# AJH_ss12144_01_4hp.net
KiCad netlist of a schematic drawn in EAGLE
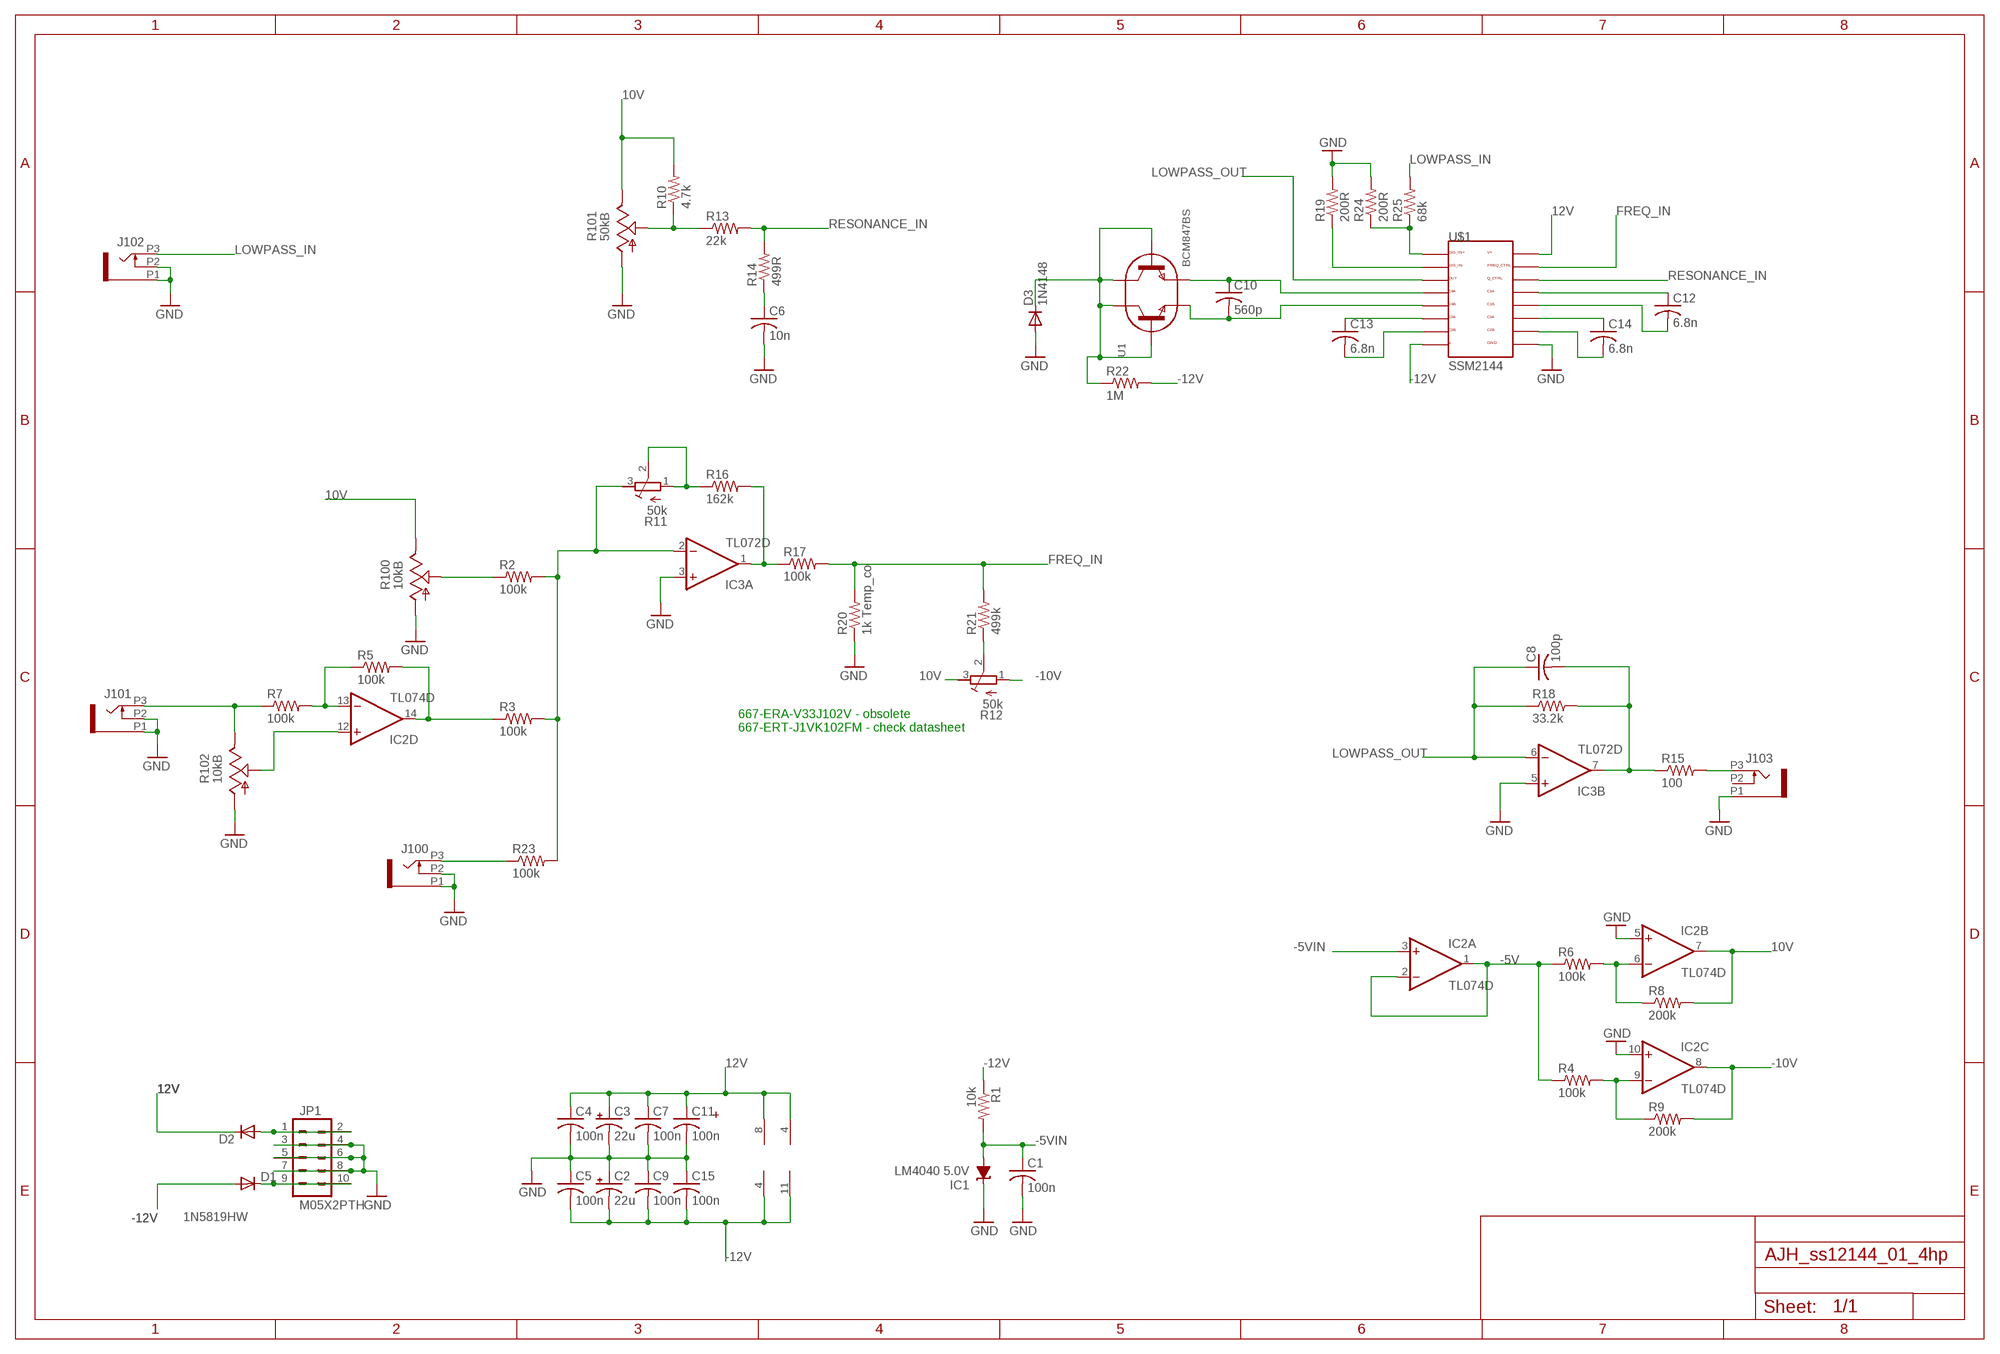
[diagram p0: schematic, sheet 1]

(export (version "E")
  (design (tool "Eeschema 10.0.6"))
  (components
    (comp (ref "C1")
      (value "100n")
      (footprint "eagle-import:C0603")
      (libsource (lib "eagle-import") (part "C-USC0603"))
    )
    (comp (ref "C2")
      (value "22u")
      (footprint "eagle-import:PANASONIC_B")
      (libsource (lib "eagle-import") (part "CPOL-USB"))
    )
    (comp (ref "C3")
      (value "22u")
      (footprint "eagle-import:PANASONIC_B")
      (libsource (lib "eagle-import") (part "CPOL-USB"))
    )
    (comp (ref "C4")
      (value "100n")
      (footprint "eagle-import:C0603")
      (libsource (lib "eagle-import") (part "C-USC0603"))
    )
    (comp (ref "C5")
      (value "100n")
      (footprint "eagle-import:C0603")
      (libsource (lib "eagle-import") (part "C-USC0603"))
    )
    (comp (ref "C6")
      (value "10n")
      (footprint "eagle-import:C0603")
      (libsource (lib "eagle-import") (part "C-USC0603"))
    )
    (comp (ref "C7")
      (value "100n")
      (footprint "eagle-import:C0603")
      (libsource (lib "eagle-import") (part "C-USC0603"))
    )
    (comp (ref "C8")
      (value "100p")
      (footprint "eagle-import:C0603")
      (libsource (lib "eagle-import") (part "C-USC0603"))
    )
    (comp (ref "C9")
      (value "100n")
      (footprint "eagle-import:C0603")
      (libsource (lib "eagle-import") (part "C-USC0603"))
    )
    (comp (ref "C10")
      (value "560p")
      (footprint "eagle-import:C0603")
      (libsource (lib "eagle-import") (part "C-USC0603"))
    )
    (comp (ref "C11")
      (value "100n")
      (footprint "eagle-import:C0603")
      (libsource (lib "eagle-import") (part "C-USC0603"))
    )
    (comp (ref "C12")
      (value "6.8n")
      (footprint "eagle-import:C0603")
      (libsource (lib "eagle-import") (part "C-USC0603"))
    )
    (comp (ref "C13")
      (value "6.8n")
      (footprint "eagle-import:C0603")
      (libsource (lib "eagle-import") (part "C-USC0603"))
    )
    (comp (ref "C14")
      (value "6.8n")
      (footprint "eagle-import:C0603")
      (libsource (lib "eagle-import") (part "C-USC0603"))
    )
    (comp (ref "C15")
      (value "100n")
      (footprint "eagle-import:C0603")
      (libsource (lib "eagle-import") (part "C-USC0603"))
    )
    (comp (ref "D1")
      (value "1N5819HW")
      (footprint "eagle-import:SOD123")
      (libsource (lib "eagle-import") (part "DIODE-SOD123"))
    )
    (comp (ref "D2")
      (value "1N5819HW")
      (footprint "eagle-import:SOD123")
      (libsource (lib "eagle-import") (part "DIODE-SOD123"))
    )
    (comp (ref "D3")
      (value "1N4148")
      (footprint "eagle-import:SOD523")
      (libsource (lib "eagle-import") (part "DIODE-SOD523"))
    )
    (comp (ref "IC1")
      (value "LM4040 5.0V")
      (footprint "eagle-import:DBZ_R-PDSO-G3")
      (libsource (lib "eagle-import") (part "LM4041DBZC12"))
    )
    (comp (ref "IC2")
      (value "TL074D")
      (footprint "eagle-import:SO14")
      (libsource (lib "eagle-import") (part "TL074D"))
    )
    (comp (ref "IC3")
      (value "TL072D")
      (footprint "eagle-import:SO08")
      (libsource (lib "eagle-import") (part "TL072D"))
    )
    (comp (ref "J100")
      (value "PJ301_THONKICONN6")
      (footprint "eagle-import:WQP_PJ_301M6")
      (libsource (lib "eagle-import") (part "PJ301_THONKICONN6"))
    )
    (comp (ref "J101")
      (value "PJ301_THONKICONN6")
      (footprint "eagle-import:WQP_PJ_301M6")
      (libsource (lib "eagle-import") (part "PJ301_THONKICONN6"))
    )
    (comp (ref "J102")
      (value "PJ301_THONKICONN6")
      (footprint "eagle-import:WQP_PJ_301M6")
      (libsource (lib "eagle-import") (part "PJ301_THONKICONN6"))
    )
    (comp (ref "J103")
      (value "PJ301_THONKICONN6")
      (footprint "eagle-import:WQP_PJ_301M6")
      (libsource (lib "eagle-import") (part "PJ301_THONKICONN6"))
    )
    (comp (ref "JP1")
      (value "M05X2PTH")
      (footprint "eagle-import:AVR_ICSP")
      (libsource (lib "eagle-import") (part "M05X2PTH"))
    )
    (comp (ref "R1")
      (value "10k")
      (footprint "eagle-import:R0603")
      (libsource (lib "eagle-import") (part "R-US_R0603"))
    )
    (comp (ref "R2")
      (value "100k")
      (footprint "eagle-import:R0603")
      (libsource (lib "eagle-import") (part "R-US_R0603"))
    )
    (comp (ref "R3")
      (value "100k")
      (footprint "eagle-import:R0603")
      (libsource (lib "eagle-import") (part "R-US_R0603"))
    )
    (comp (ref "R4")
      (value "100k")
      (footprint "eagle-import:R0603")
      (libsource (lib "eagle-import") (part "R-US_R0603"))
    )
    (comp (ref "R5")
      (value "100k")
      (footprint "eagle-import:R0603")
      (libsource (lib "eagle-import") (part "R-US_R0603"))
    )
    (comp (ref "R6")
      (value "100k")
      (footprint "eagle-import:R0603")
      (libsource (lib "eagle-import") (part "R-US_R0603"))
    )
    (comp (ref "R7")
      (value "100k")
      (footprint "eagle-import:R0603")
      (libsource (lib "eagle-import") (part "R-US_R0603"))
    )
    (comp (ref "R8")
      (value "200k")
      (footprint "eagle-import:R0603")
      (libsource (lib "eagle-import") (part "R-US_R0603"))
    )
    (comp (ref "R9")
      (value "200k")
      (footprint "eagle-import:R0603")
      (libsource (lib "eagle-import") (part "R-US_R0603"))
    )
    (comp (ref "R10")
      (value "4.7k")
      (footprint "eagle-import:R0603")
      (libsource (lib "eagle-import") (part "R-US_R0603"))
    )
    (comp (ref "R11")
      (value "50k")
      (footprint "eagle-import:RTRIM3296X")
      (libsource (lib "eagle-import") (part "R-TRIMM3296X"))
    )
    (comp (ref "R12")
      (value "50k")
      (footprint "eagle-import:RTRIM3296X")
      (libsource (lib "eagle-import") (part "R-TRIMM3296X"))
    )
    (comp (ref "R13")
      (value "22k")
      (footprint "eagle-import:R0603")
      (libsource (lib "eagle-import") (part "R-US_R0603"))
    )
    (comp (ref "R14")
      (value "499R")
      (footprint "eagle-import:R0603")
      (libsource (lib "eagle-import") (part "R-US_R0603"))
    )
    (comp (ref "R15")
      (value "100")
      (footprint "eagle-import:R0603")
      (libsource (lib "eagle-import") (part "R-US_R0603"))
    )
    (comp (ref "R16")
      (value "162k")
      (footprint "eagle-import:R0603")
      (libsource (lib "eagle-import") (part "R-US_R0603"))
    )
    (comp (ref "R17")
      (value "100k")
      (footprint "eagle-import:R0603")
      (libsource (lib "eagle-import") (part "R-US_R0603"))
    )
    (comp (ref "R18")
      (value "33.2k")
      (footprint "eagle-import:R0603")
      (libsource (lib "eagle-import") (part "R-US_R0603"))
    )
    (comp (ref "R19")
      (value "200R")
      (footprint "eagle-import:R0603")
      (libsource (lib "eagle-import") (part "R-US_R0603"))
    )
    (comp (ref "R20")
      (value "1k Temp_co")
      (footprint "eagle-import:R0603")
      (libsource (lib "eagle-import") (part "R-US_R0603"))
    )
    (comp (ref "R21")
      (value "499k")
      (footprint "eagle-import:R0603")
      (libsource (lib "eagle-import") (part "R-US_R0603"))
    )
    (comp (ref "R22")
      (value "1M")
      (footprint "eagle-import:R0603")
      (libsource (lib "eagle-import") (part "R-US_R0603"))
    )
    (comp (ref "R23")
      (value "100k")
      (footprint "eagle-import:R0603")
      (libsource (lib "eagle-import") (part "R-US_R0603"))
    )
    (comp (ref "R24")
      (value "200R")
      (footprint "eagle-import:R0603")
      (libsource (lib "eagle-import") (part "R-US_R0603"))
    )
    (comp (ref "R25")
      (value "68k")
      (footprint "eagle-import:R0603")
      (libsource (lib "eagle-import") (part "R-US_R0603"))
    )
    (comp (ref "R100")
      (value "10kB")
      (footprint "eagle-import:ALPS_POT_VERTICAL")
      (libsource (lib "eagle-import") (part "POT_USVERTICAL"))
    )
    (comp (ref "R101")
      (value "50kB")
      (footprint "eagle-import:ALPS_POT_VERTICAL")
      (libsource (lib "eagle-import") (part "POT_USVERTICAL"))
    )
    (comp (ref "R102")
      (value "10kB")
      (footprint "eagle-import:ALPS_POT_VERTICAL")
      (libsource (lib "eagle-import") (part "POT_USVERTICAL"))
    )
    (comp (ref "U$1")
      (value "SSM2144")
      (footprint "eagle-import:SSOP16")
      (libsource (lib "eagle-import") (part "SSM2144"))
    )
    (comp (ref "U1")
      (value "BCM847BS")
      (footprint "eagle-import:SOT363")
      (libsource (lib "eagle-import") (part "BCM847BS"))
    )
  )
  (nets
    (net (code "1") (name "/-5V") (class "Default")
      (node (ref "IC2") (pin "1") (pinfunction "OUT_1") (pintype "output"))
      (node (ref "IC2") (pin "2") (pinfunction "-IN_2") (pintype "input"))
      (node (ref "R4") (pin "1") (pinfunction "1_1") (pintype "passive"))
      (node (ref "R6") (pin "1") (pinfunction "1_1") (pintype "passive"))
    )
    (net (code "2") (name "/-5VIN") (class "Default")
      (node (ref "C1") (pin "1") (pinfunction "1_1") (pintype "passive"))
      (node (ref "IC1") (pin "2") (pinfunction "A_2") (pintype "passive"))
      (node (ref "IC2") (pin "3") (pinfunction "+IN_3") (pintype "input"))
      (node (ref "R1") (pin "2") (pinfunction "2_2") (pintype "passive"))
    )
    (net (code "3") (name "/-10V") (class "Default")
      (node (ref "IC2") (pin "8") (pinfunction "OUT_8") (pintype "output"))
      (node (ref "R12") (pin "1") (pinfunction "E_1") (pintype "passive"))
      (node (ref "R9") (pin "2") (pinfunction "2_2") (pintype "passive"))
    )
    (net (code "4") (name "/-12V") (class "Default")
      (node (ref "C15") (pin "2") (pinfunction "2_2") (pintype "passive"))
      (node (ref "C2") (pin "-") (pinfunction "-_-") (pintype "passive"))
      (node (ref "C5") (pin "2") (pinfunction "2_2") (pintype "passive"))
      (node (ref "C9") (pin "2") (pinfunction "2_2") (pintype "passive"))
      (node (ref "D1") (pin "A") (pinfunction "A_A") (pintype "passive"))
      (node (ref "IC2") (pin "11") (pinfunction "V-_11") (pintype "power_in"))
      (node (ref "IC3") (pin "4") (pinfunction "V-_4") (pintype "power_in"))
      (node (ref "R1") (pin "1") (pinfunction "1_1") (pintype "passive"))
      (node (ref "R22") (pin "2") (pinfunction "2_2") (pintype "passive"))
      (node (ref "U$1") (pin "8") (pinfunction "V-_8") (pintype "bidirectional"))
    )
    (net (code "5") (name "/10V") (class "Default")
      (node (ref "IC2") (pin "7") (pinfunction "OUT_7") (pintype "output"))
      (node (ref "R10") (pin "2") (pinfunction "2_2") (pintype "passive"))
      (node (ref "R100") (pin "P$1") (pinfunction "E_P$1") (pintype "passive"))
      (node (ref "R101") (pin "P$1") (pinfunction "E_P$1") (pintype "passive"))
      (node (ref "R12") (pin "3") (pinfunction "A_3") (pintype "passive"))
      (node (ref "R8") (pin "2") (pinfunction "2_2") (pintype "passive"))
    )
    (net (code "6") (name "/12V") (class "Default")
      (node (ref "C11") (pin "1") (pinfunction "1_1") (pintype "passive"))
      (node (ref "C3") (pin "+") (pinfunction "+_+") (pintype "passive"))
      (node (ref "C4") (pin "1") (pinfunction "1_1") (pintype "passive"))
      (node (ref "C7") (pin "1") (pinfunction "1_1") (pintype "passive"))
      (node (ref "D2") (pin "C") (pinfunction "C_C") (pintype "passive"))
      (node (ref "IC2") (pin "4") (pinfunction "V+_4") (pintype "power_in"))
      (node (ref "IC3") (pin "8") (pinfunction "V+_8") (pintype "power_in"))
      (node (ref "U$1") (pin "16") (pinfunction "V+_16") (pintype "bidirectional"))
    )
    (net (code "7") (name "/FREQ_IN") (class "Default")
      (node (ref "R17") (pin "2") (pinfunction "2_2") (pintype "passive"))
      (node (ref "R20") (pin "2") (pinfunction "2_2") (pintype "passive"))
      (node (ref "R21") (pin "2") (pinfunction "2_2") (pintype "passive"))
      (node (ref "U$1") (pin "15") (pinfunction "FREQ_CTRL_15") (pintype "bidirectional"))
    )
    (net (code "8") (name "/LOWPASS_IN") (class "Default")
      (node (ref "J102") (pin "P3") (pinfunction "3_P3") (pintype "passive"))
      (node (ref "R25") (pin "2") (pinfunction "2_2") (pintype "passive"))
    )
    (net (code "9") (name "/LOWPASS_OUT") (class "Default")
      (node (ref "C8") (pin "1") (pinfunction "1_1") (pintype "passive"))
      (node (ref "IC3") (pin "6") (pinfunction "-IN_6") (pintype "input"))
      (node (ref "R18") (pin "1") (pinfunction "1_1") (pintype "passive"))
      (node (ref "U$1") (pin "3") (pinfunction "OUT_3") (pintype "bidirectional"))
    )
    (net (code "10") (name "/RESONANCE_IN") (class "Default")
      (node (ref "R13") (pin "2") (pinfunction "2_2") (pintype "passive"))
      (node (ref "R14") (pin "2") (pinfunction "2_2") (pintype "passive"))
      (node (ref "U$1") (pin "14") (pinfunction "Q_CTRL_14") (pintype "bidirectional"))
    )
    (net (code "11") (name "GND") (class "Default")
      (node (ref "C1") (pin "2") (pinfunction "2_2") (pintype "passive"))
      (node (ref "C11") (pin "2") (pinfunction "2_2") (pintype "passive"))
      (node (ref "C15") (pin "1") (pinfunction "1_1") (pintype "passive"))
      (node (ref "C2") (pin "+") (pinfunction "+_+") (pintype "passive"))
      (node (ref "C3") (pin "-") (pinfunction "-_-") (pintype "passive"))
      (node (ref "C4") (pin "2") (pinfunction "2_2") (pintype "passive"))
      (node (ref "C5") (pin "1") (pinfunction "1_1") (pintype "passive"))
      (node (ref "C6") (pin "2") (pinfunction "2_2") (pintype "passive"))
      (node (ref "C7") (pin "2") (pinfunction "2_2") (pintype "passive"))
      (node (ref "C9") (pin "1") (pinfunction "1_1") (pintype "passive"))
      (node (ref "D3") (pin "A") (pinfunction "A_A") (pintype "passive"))
      (node (ref "IC1") (pin "1") (pinfunction "C_1") (pintype "passive"))
      (node (ref "IC2") (pin "10") (pinfunction "+IN_10") (pintype "input"))
      (node (ref "IC2") (pin "5") (pinfunction "+IN_5") (pintype "input"))
      (node (ref "IC3") (pin "3") (pinfunction "+IN_3") (pintype "input"))
      (node (ref "IC3") (pin "5") (pinfunction "+IN_5") (pintype "input"))
      (node (ref "J100") (pin "P1") (pinfunction "1_P1") (pintype "passive"))
      (node (ref "J100") (pin "P2") (pinfunction "2_P2") (pintype "passive"))
      (node (ref "J101") (pin "P1") (pinfunction "1_P1") (pintype "passive"))
      (node (ref "J101") (pin "P2") (pinfunction "2_P2") (pintype "passive"))
      (node (ref "J102") (pin "P1") (pinfunction "1_P1") (pintype "passive"))
      (node (ref "J102") (pin "P2") (pinfunction "2_P2") (pintype "passive"))
      (node (ref "J103") (pin "P1") (pinfunction "1_P1") (pintype "passive"))
      (node (ref "JP1") (pin "3") (pinfunction "3_3") (pintype "passive"))
      (node (ref "JP1") (pin "4") (pinfunction "4_4") (pintype "passive"))
      (node (ref "JP1") (pin "5") (pinfunction "5_5") (pintype "passive"))
      (node (ref "JP1") (pin "6") (pinfunction "6_6") (pintype "passive"))
      (node (ref "JP1") (pin "7") (pinfunction "7_7") (pintype "passive"))
      (node (ref "JP1") (pin "8") (pinfunction "8_8") (pintype "passive"))
      (node (ref "R100") (pin "P$3") (pinfunction "A_P$3") (pintype "passive"))
      (node (ref "R101") (pin "P$3") (pinfunction "A_P$3") (pintype "passive"))
      (node (ref "R102") (pin "P$3") (pinfunction "A_P$3") (pintype "passive"))
      (node (ref "R19") (pin "2") (pinfunction "2_2") (pintype "passive"))
      (node (ref "R20") (pin "1") (pinfunction "1_1") (pintype "passive"))
      (node (ref "R24") (pin "2") (pinfunction "2_2") (pintype "passive"))
      (node (ref "U$1") (pin "9") (pinfunction "GND_9") (pintype "bidirectional"))
    )
    (net (code "12") (name "Net-(C6-Pad1)") (class "Default")
      (node (ref "C6") (pin "1") (pinfunction "1_1") (pintype "passive"))
      (node (ref "R14") (pin "1") (pinfunction "1_1") (pintype "passive"))
    )
    (net (code "13") (name "Net-(D1-PadC)") (class "Default")
      (node (ref "D1") (pin "C") (pinfunction "C_C") (pintype "passive"))
      (node (ref "JP1") (pin "10") (pinfunction "10_10") (pintype "passive"))
      (node (ref "JP1") (pin "9") (pinfunction "9_9") (pintype "passive"))
    )
    (net (code "14") (name "Net-(D2-PadA)") (class "Default")
      (node (ref "D2") (pin "A") (pinfunction "A_A") (pintype "passive"))
      (node (ref "JP1") (pin "1") (pinfunction "1_1") (pintype "passive"))
      (node (ref "JP1") (pin "2") (pinfunction "2_2") (pintype "passive"))
    )
    (net (code "15") (name "Net-(IC2B--IN)") (class "Default")
      (node (ref "IC2") (pin "6") (pinfunction "-IN_6") (pintype "input"))
      (node (ref "R6") (pin "2") (pinfunction "2_2") (pintype "passive"))
      (node (ref "R8") (pin "1") (pinfunction "1_1") (pintype "passive"))
    )
    (net (code "16") (name "Net-(IC2C--IN)") (class "Default")
      (node (ref "IC2") (pin "9") (pinfunction "-IN_9") (pintype "input"))
      (node (ref "R4") (pin "2") (pinfunction "2_2") (pintype "passive"))
      (node (ref "R9") (pin "1") (pinfunction "1_1") (pintype "passive"))
    )
    (net (code "17") (name "Net-(IC2D-+IN)") (class "Default")
      (node (ref "IC2") (pin "12") (pinfunction "+IN_12") (pintype "input"))
      (node (ref "R102") (pin "P$2") (pinfunction "S_P$2") (pintype "passive"))
    )
    (net (code "18") (name "Net-(IC2D--IN)") (class "Default")
      (node (ref "IC2") (pin "13") (pinfunction "-IN_13") (pintype "input"))
      (node (ref "R5") (pin "1") (pinfunction "1_1") (pintype "passive"))
      (node (ref "R7") (pin "2") (pinfunction "2_2") (pintype "passive"))
    )
    (net (code "19") (name "Net-(IC2D-OUT)") (class "Default")
      (node (ref "IC2") (pin "14") (pinfunction "OUT_14") (pintype "output"))
      (node (ref "R3") (pin "1") (pinfunction "1_1") (pintype "passive"))
      (node (ref "R5") (pin "2") (pinfunction "2_2") (pintype "passive"))
    )
    (net (code "20") (name "Net-(IC3A--IN)") (class "Default")
      (node (ref "IC3") (pin "2") (pinfunction "-IN_2") (pintype "input"))
      (node (ref "R11") (pin "3") (pinfunction "A_3") (pintype "passive"))
      (node (ref "R2") (pin "2") (pinfunction "2_2") (pintype "passive"))
      (node (ref "R23") (pin "2") (pinfunction "2_2") (pintype "passive"))
      (node (ref "R3") (pin "2") (pinfunction "2_2") (pintype "passive"))
    )
    (net (code "21") (name "Net-(IC3A-OUT)") (class "Default")
      (node (ref "IC3") (pin "1") (pinfunction "OUT_1") (pintype "output"))
      (node (ref "R16") (pin "2") (pinfunction "2_2") (pintype "passive"))
      (node (ref "R17") (pin "1") (pinfunction "1_1") (pintype "passive"))
    )
    (net (code "22") (name "Net-(IC3B-OUT)") (class "Default")
      (node (ref "C8") (pin "2") (pinfunction "2_2") (pintype "passive"))
      (node (ref "IC3") (pin "7") (pinfunction "OUT_7") (pintype "output"))
      (node (ref "R15") (pin "1") (pinfunction "1_1") (pintype "passive"))
      (node (ref "R18") (pin "2") (pinfunction "2_2") (pintype "passive"))
    )
    (net (code "23") (name "Net-(J100-3)") (class "Default")
      (node (ref "J100") (pin "P3") (pinfunction "3_P3") (pintype "passive"))
      (node (ref "R23") (pin "1") (pinfunction "1_1") (pintype "passive"))
    )
    (net (code "24") (name "Net-(J101-3)") (class "Default")
      (node (ref "J101") (pin "P3") (pinfunction "3_P3") (pintype "passive"))
      (node (ref "R102") (pin "P$1") (pinfunction "E_P$1") (pintype "passive"))
      (node (ref "R7") (pin "1") (pinfunction "1_1") (pintype "passive"))
    )
    (net (code "25") (name "Net-(J103-3)") (class "Default")
      (node (ref "J103") (pin "P3") (pinfunction "3_P3") (pintype "passive"))
      (node (ref "R15") (pin "2") (pinfunction "2_2") (pintype "passive"))
    )
    (net (code "26") (name "Net-(R11-E)") (class "Default")
      (node (ref "R11") (pin "1") (pinfunction "E_1") (pintype "passive"))
      (node (ref "R11") (pin "2") (pinfunction "S_2") (pintype "passive"))
      (node (ref "R16") (pin "1") (pinfunction "1_1") (pintype "passive"))
    )
    (net (code "27") (name "Net-(R12-S)") (class "Default")
      (node (ref "R12") (pin "2") (pinfunction "S_2") (pintype "passive"))
      (node (ref "R21") (pin "1") (pinfunction "1_1") (pintype "passive"))
    )
    (net (code "28") (name "Net-(R100-S)") (class "Default")
      (node (ref "R100") (pin "P$2") (pinfunction "S_P$2") (pintype "passive"))
      (node (ref "R2") (pin "1") (pinfunction "1_1") (pintype "passive"))
    )
    (net (code "29") (name "Net-(R101-S)") (class "Default")
      (node (ref "R10") (pin "1") (pinfunction "1_1") (pintype "passive"))
      (node (ref "R101") (pin "P$2") (pinfunction "S_P$2") (pintype "passive"))
      (node (ref "R13") (pin "1") (pinfunction "1_1") (pintype "passive"))
    )
    (net (code "30") (name "Net-(U$1-C1A)") (class "Default")
      (node (ref "C12") (pin "1") (pinfunction "1_1") (pintype "passive"))
      (node (ref "U$1") (pin "13") (pinfunction "C1A_13") (pintype "bidirectional"))
    )
    (net (code "31") (name "Net-(U$1-C1B)") (class "Default")
      (node (ref "C12") (pin "2") (pinfunction "2_2") (pintype "passive"))
      (node (ref "U$1") (pin "12") (pinfunction "C1B_12") (pintype "bidirectional"))
    )
    (net (code "32") (name "Net-(U$1-C2A)") (class "Default")
      (node (ref "C14") (pin "1") (pinfunction "1_1") (pintype "passive"))
      (node (ref "U$1") (pin "11") (pinfunction "C2A_11") (pintype "bidirectional"))
    )
    (net (code "33") (name "Net-(U$1-C2B)") (class "Default")
      (node (ref "C14") (pin "2") (pinfunction "2_2") (pintype "passive"))
      (node (ref "U$1") (pin "10") (pinfunction "C2B_10") (pintype "bidirectional"))
    )
    (net (code "34") (name "Net-(U$1-C3A)") (class "Default")
      (node (ref "C13") (pin "1") (pinfunction "1_1") (pintype "passive"))
      (node (ref "U$1") (pin "6") (pinfunction "C3A_6") (pintype "bidirectional"))
    )
    (net (code "35") (name "Net-(U$1-C3B)") (class "Default")
      (node (ref "C13") (pin "2") (pinfunction "2_2") (pintype "passive"))
      (node (ref "U$1") (pin "7") (pinfunction "C3B_7") (pintype "bidirectional"))
    )
    (net (code "36") (name "Net-(U$1-C4A)") (class "Default")
      (node (ref "C10") (pin "1") (pinfunction "1_1") (pintype "passive"))
      (node (ref "U$1") (pin "4") (pinfunction "C4A_4") (pintype "bidirectional"))
      (node (ref "U1") (pin "4") (pinfunction "E2_4") (pintype "passive"))
    )
    (net (code "37") (name "Net-(U$1-C4B)") (class "Default")
      (node (ref "C10") (pin "2") (pinfunction "2_2") (pintype "passive"))
      (node (ref "U$1") (pin "5") (pinfunction "C4B_5") (pintype "bidirectional"))
      (node (ref "U1") (pin "1") (pinfunction "E1_1") (pintype "passive"))
    )
    (net (code "38") (name "Net-(U$1-SIG_IN+)") (class "Default")
      (node (ref "R24") (pin "1") (pinfunction "1_1") (pintype "passive"))
      (node (ref "R25") (pin "1") (pinfunction "1_1") (pintype "passive"))
      (node (ref "U$1") (pin "1") (pinfunction "SIG_IN+_1") (pintype "bidirectional"))
    )
    (net (code "39") (name "Net-(U$1-SIG_IN-)") (class "Default")
      (node (ref "R19") (pin "1") (pinfunction "1_1") (pintype "passive"))
      (node (ref "U$1") (pin "2") (pinfunction "SIG_IN-_2") (pintype "bidirectional"))
    )
    (net (code "40") (name "Net-(U1-B1)") (class "Default")
      (node (ref "D3") (pin "C") (pinfunction "C_C") (pintype "passive"))
      (node (ref "R22") (pin "1") (pinfunction "1_1") (pintype "passive"))
      (node (ref "U1") (pin "2") (pinfunction "B1_2") (pintype "passive"))
      (node (ref "U1") (pin "3") (pinfunction "C2_3") (pintype "passive"))
      (node (ref "U1") (pin "5") (pinfunction "B2_5") (pintype "passive"))
      (node (ref "U1") (pin "6") (pinfunction "C1_6") (pintype "passive"))
    )
    (net (code "41") (name "unconnected-(J103-2-PadP2)") (class "Default")
      (node (ref "J103") (pin "P2") (pinfunction "2_P2") (pintype "passive"))
    )
  )
)
